# design.net
KiCad netlist of a schematic drawn in Altium Designer
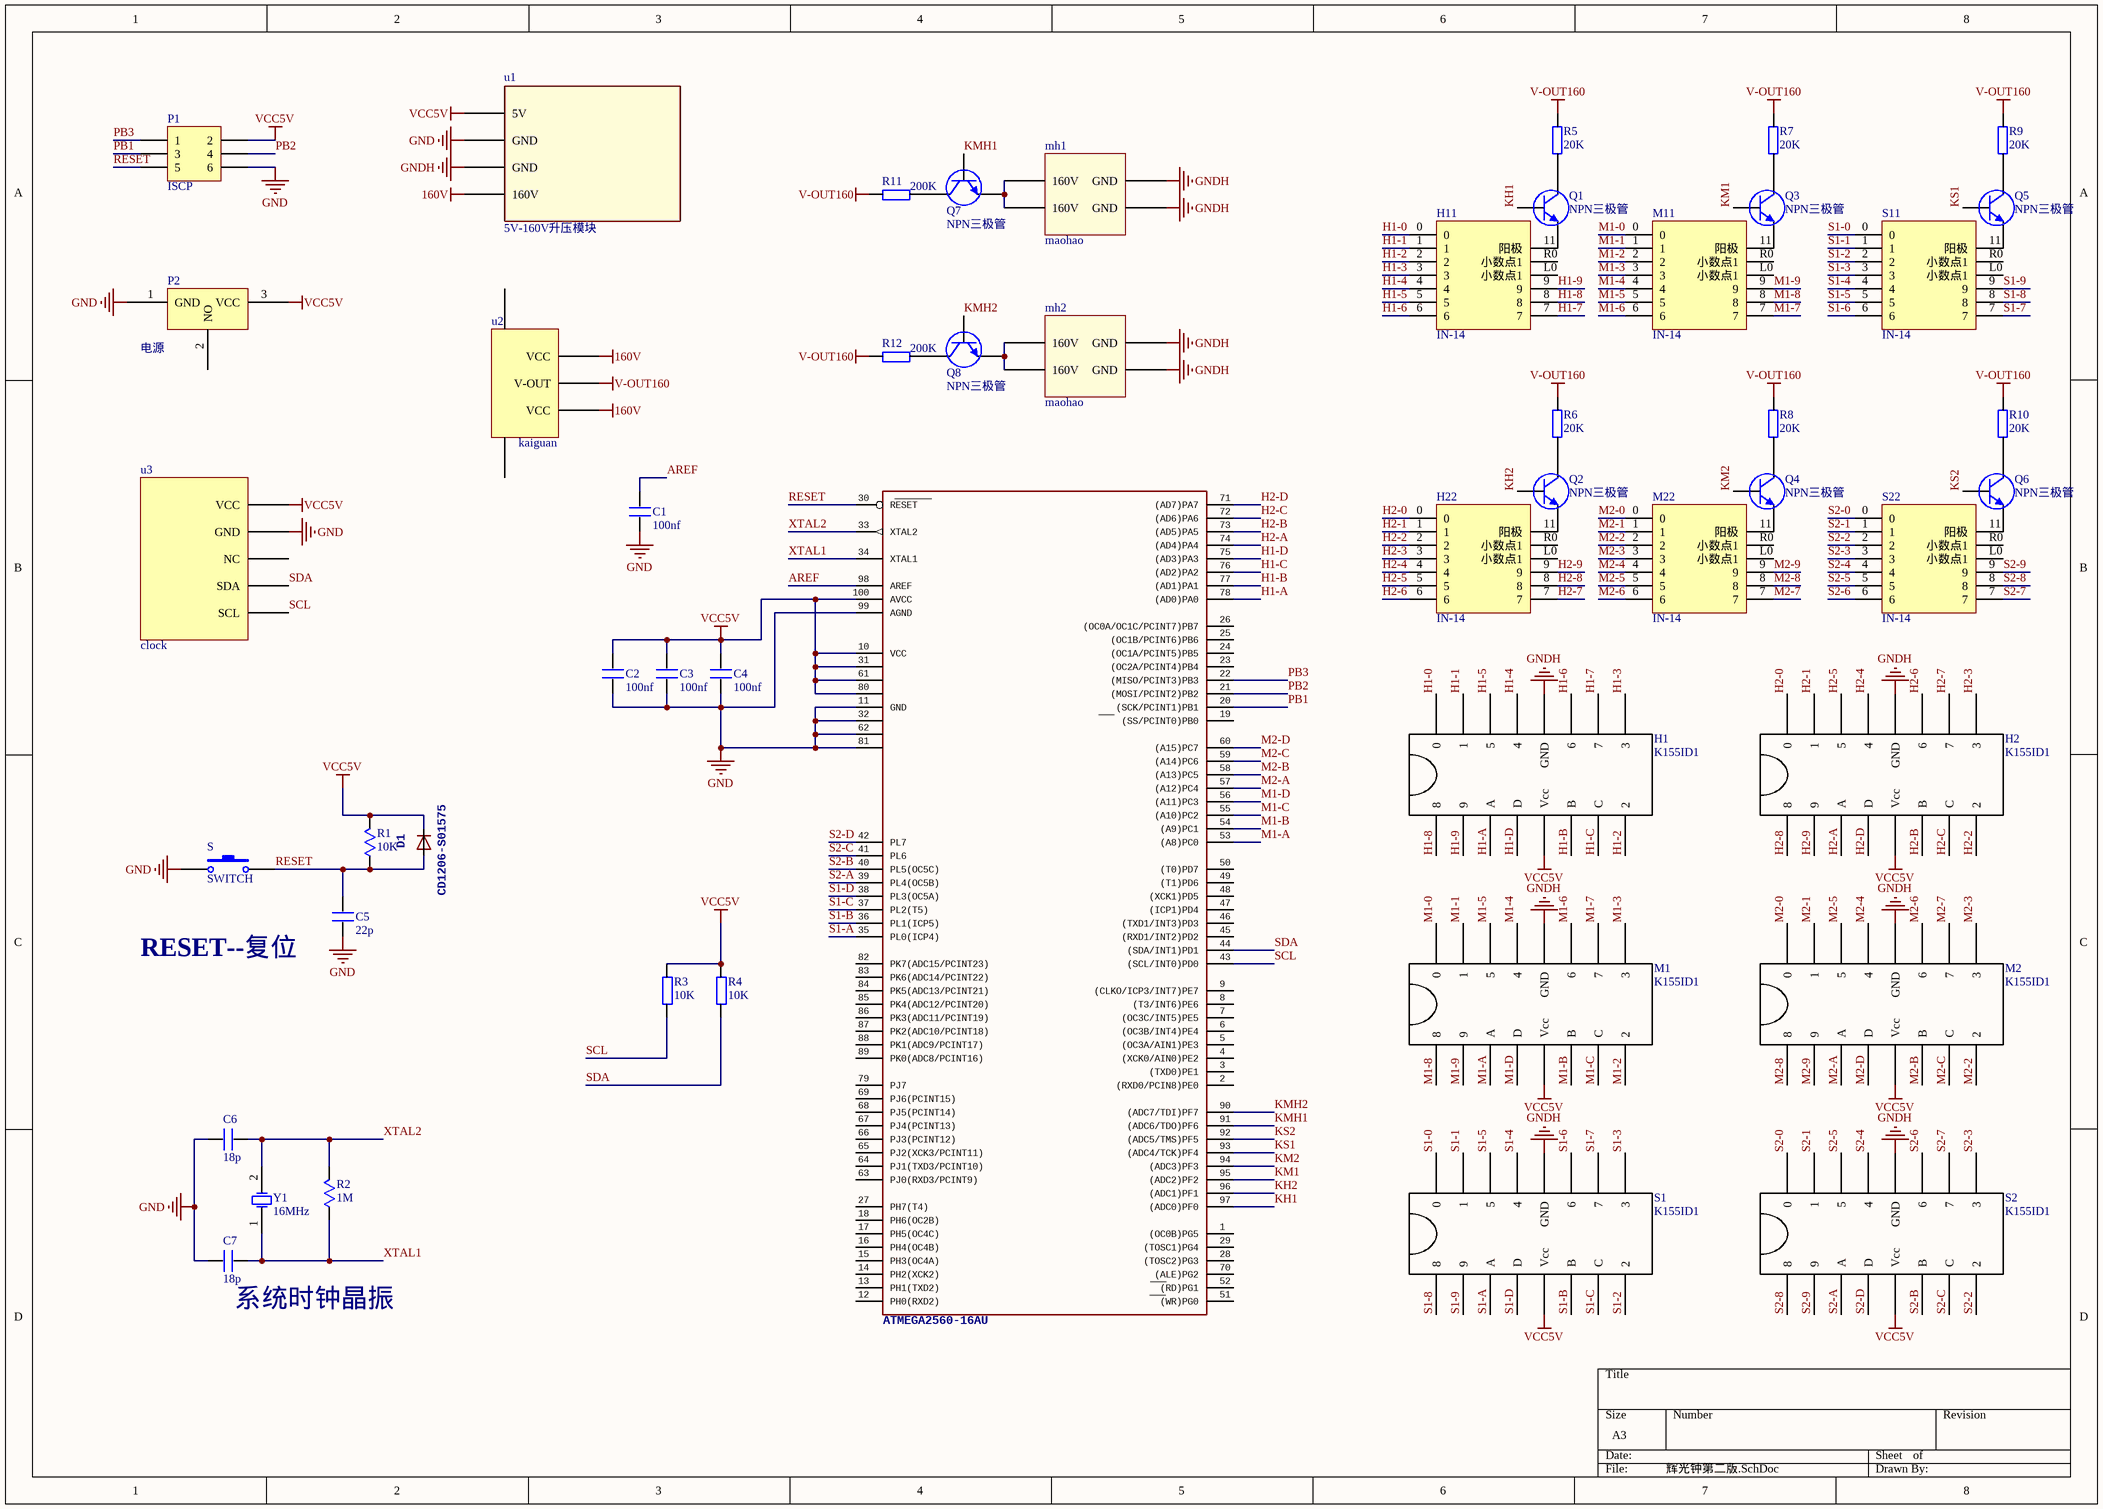
[diagram p0: 辉光钟第二版.SchDoc]

(export (version "E")
  (design (tool "Eeschema 10.0.6"))
  (components
    (comp (ref "C1") (value "100nf") (footprint "0805") (libsource (lib "STM32封装库") (part "C")))
    (comp (ref "C2") (value "100nf") (footprint "0805") (libsource (lib "STM32封装库") (part "C")))
    (comp (ref "C3") (value "100nf") (footprint "0805") (libsource (lib "STM32封装库") (part "C")))
    (comp (ref "C4") (value "100nf") (footprint "0805") (libsource (lib "STM32封装库") (part "C")))
    (comp (ref "C5") (value "22p") (footprint "0805") (libsource (lib "STM32封装库") (part "C_3")))
    (comp (ref "C6") (value "18p") (footprint "0805") (libsource (lib "STM32封装库") (part "C_1")))
    (comp (ref "C7") (value "18p") (footprint "0805") (libsource (lib "STM32封装库") (part "C_1")))
    (comp (ref "D1")
      (value "CD1206-S01575")
      (footprint "MINIMELF")
      (description "<b>DIODE</b>")
      (libsource (lib "Arduino_MEGA_2560-Rev3") (part "DIODE-MINIMELF"))
    )
    (comp (ref "H1")
      (value "K155ID1")
      (footprint "Miscellaneous Devices:DIP-16")
      (libsource (lib "辉光钟第二版") (part "K155ID1"))
    )
    (comp (ref "H2")
      (value "K155ID1")
      (footprint "Miscellaneous Devices:DIP-16")
      (libsource (lib "辉光钟第二版") (part "K155ID1"))
    )
    (comp (ref "H11") (value "IN-14") (footprint "IN-14") (libsource (lib "辉光管时钟V2.0") (part "IN-14")))
    (comp (ref "H22") (value "IN-14") (footprint "IN-14") (libsource (lib "辉光管时钟V2.0") (part "IN-14")))
    (comp (ref "M1")
      (value "K155ID1")
      (footprint "Miscellaneous Devices:DIP-16")
      (libsource (lib "辉光钟第二版") (part "K155ID1"))
    )
    (comp (ref "M2")
      (value "K155ID1")
      (footprint "Miscellaneous Devices:DIP-16")
      (libsource (lib "辉光钟第二版") (part "K155ID1"))
    )
    (comp (ref "M11") (value "IN-14") (footprint "IN-14") (libsource (lib "辉光管时钟V2.0") (part "IN-14")))
    (comp (ref "M22") (value "IN-14") (footprint "IN-14") (libsource (lib "辉光管时钟V2.0") (part "IN-14")))
    (comp (ref "mh1")
      (value "maohao")
      (footprint "maohao:PCBComponent_1")
      (libsource (lib "辉光钟第二版") (part "maohao"))
    )
    (comp (ref "mh2")
      (value "maohao")
      (footprint "maohao:PCBComponent_1")
      (libsource (lib "辉光钟第二版") (part "maohao"))
    )
    (comp (ref "P1")
      (value "ISCP")
      (footprint "HDR2X3")
      (description "Header, 3-Pin, Dual row")
      (fields (field (name "PUBLISHER") "Altium Limited"))
      (libsource (lib "Miscellaneous Connectors") (part "Header 3X2"))
    )
    (comp (ref "P2") (value "电源") (footprint "DC5.5-2.1") (libsource (lib "常用元件库") (part "dc5.5-2.1")))
    (comp (ref "Q1")
      (value "NPN三极管")
      (footprint "TO-92")
      (description "NPN")
      (fields (field (name "PUBLISHER") "Altium Limited"))
      (libsource (lib "三极管集成库") (part "NPN三极管_1"))
    )
    (comp (ref "Q2")
      (value "NPN三极管")
      (footprint "TO-92")
      (description "NPN")
      (fields (field (name "PUBLISHER") "Altium Limited"))
      (libsource (lib "三极管集成库") (part "NPN三极管_1"))
    )
    (comp (ref "Q3")
      (value "NPN三极管")
      (footprint "TO-92")
      (description "NPN")
      (fields (field (name "PUBLISHER") "Altium Limited"))
      (libsource (lib "三极管集成库") (part "NPN三极管_1"))
    )
    (comp (ref "Q4")
      (value "NPN三极管")
      (footprint "TO-92")
      (description "NPN")
      (fields (field (name "PUBLISHER") "Altium Limited"))
      (libsource (lib "三极管集成库") (part "NPN三极管_1"))
    )
    (comp (ref "Q5")
      (value "NPN三极管")
      (footprint "TO-92")
      (description "NPN")
      (fields (field (name "PUBLISHER") "Altium Limited"))
      (libsource (lib "三极管集成库") (part "NPN三极管_1"))
    )
    (comp (ref "Q6")
      (value "NPN三极管")
      (footprint "TO-92")
      (description "NPN")
      (fields (field (name "PUBLISHER") "Altium Limited"))
      (libsource (lib "三极管集成库") (part "NPN三极管_1"))
    )
    (comp (ref "Q7")
      (value "NPN三极管")
      (footprint "TO-92")
      (description "NPN")
      (fields (field (name "PUBLISHER") "Altium Limited"))
      (libsource (lib "三极管集成库") (part "NPN三极管_1"))
    )
    (comp (ref "Q8")
      (value "NPN三极管")
      (footprint "TO-92")
      (description "NPN")
      (fields (field (name "PUBLISHER") "Altium Limited"))
      (libsource (lib "三极管集成库") (part "NPN三极管_1"))
    )
    (comp (ref "R1") (value "10K") (footprint "0805") (libsource (lib "YT1_SCH_99SE") (part "RES")))
    (comp (ref "R2") (value "1M") (footprint "0805") (libsource (lib "YT1_SCH_99SE") (part "RES")))
    (comp (ref "R3") (value "10K") (footprint "0805") (libsource (lib "STM32封装库") (part "R")))
    (comp (ref "R4") (value "10K") (footprint "0805") (libsource (lib "STM32封装库") (part "R")))
    (comp (ref "R5") (value "20K") (footprint "0805") (libsource (lib "STM32封装库") (part "R")))
    (comp (ref "R6") (value "20K") (footprint "0805") (libsource (lib "STM32封装库") (part "R")))
    (comp (ref "R7") (value "20K") (footprint "0805") (libsource (lib "STM32封装库") (part "R")))
    (comp (ref "R8") (value "20K") (footprint "0805") (libsource (lib "STM32封装库") (part "R")))
    (comp (ref "R9") (value "20K") (footprint "0805") (libsource (lib "STM32封装库") (part "R")))
    (comp (ref "R10") (value "20K") (footprint "0805") (libsource (lib "STM32封装库") (part "R")))
    (comp (ref "R11") (value "200K") (footprint "0805") (libsource (lib "STM32封装库") (part "R")))
    (comp (ref "R12") (value "200K") (footprint "0805") (libsource (lib "STM32封装库") (part "R")))
    (comp (ref "S") (value "SWITCH") (footprint "SWITCH") (libsource (lib "STM32封装库") (part "SWITCH")))
    (comp (ref "S1")
      (value "K155ID1")
      (footprint "Miscellaneous Devices:DIP-16")
      (libsource (lib "辉光钟第二版") (part "K155ID1"))
    )
    (comp (ref "S2")
      (value "K155ID1")
      (footprint "Miscellaneous Devices:DIP-16")
      (libsource (lib "辉光钟第二版") (part "K155ID1"))
    )
    (comp (ref "S11") (value "IN-14") (footprint "IN-14") (libsource (lib "辉光管时钟V2.0") (part "IN-14")))
    (comp (ref "S22") (value "IN-14") (footprint "IN-14") (libsource (lib "辉光管时钟V2.0") (part "IN-14")))
    (comp (ref "u0")
      (value "ATMEGA2560-16AU")
      (footprint "TQFP100")
      (libsource (lib "Arduino_MEGA_2560-Rev3") (part "ATMEGA2560AU"))
    )
    (comp (ref "u1")
      (value "5V-160V升压模块")
      (footprint "5-160:PCBComponent_1")
      (libsource (lib "辉光钟第二版") (part "5-160"))
    )
    (comp (ref "u2")
      (value "kaiguan")
      (footprint "kaiguan:PCBComponent_1")
      (libsource (lib "辉光钟第二版") (part "kaiguan"))
    )
    (comp (ref "u3")
      (value "clock")
      (footprint "clock:PCBComponent_1")
      (libsource (lib "辉光钟第二版") (part "clock"))
    )
    (comp (ref "Y1")
      (value "16MHz")
      (footprint "XTAL_US")
      (description "Crystal Oscillator")
      (fields (field (name "PUBLISHER") "Altium Limited"))
      (libsource (lib "STM32封装库") (part "XTAL"))
    )
  )
  (nets
    (net (code "1") (name "/AREF") (class "Default")
      (node (ref "C1") (pin "2") (pintype "passive"))
      (node (ref "u0") (pin "98") (pinfunction "AREF_98") (pintype "passive"))
    )
    (net (code "2") (name "/H1-0") (class "Default")
      (node (ref "H1") (pin "16") (pinfunction "0_16") (pintype "passive"))
      (node (ref "H11") (pin "0") (pinfunction "0_0") (pintype "passive"))
    )
    (net (code "3") (name "/H1-1") (class "Default")
      (node (ref "H1") (pin "15") (pinfunction "1_15") (pintype "passive"))
      (node (ref "H11") (pin "1") (pinfunction "1_1") (pintype "passive"))
    )
    (net (code "4") (name "/H1-2") (class "Default")
      (node (ref "H1") (pin "8") (pinfunction "2_8") (pintype "passive"))
      (node (ref "H11") (pin "2") (pinfunction "2_2") (pintype "passive"))
    )
    (net (code "5") (name "/H1-3") (class "Default")
      (node (ref "H1") (pin "9") (pinfunction "3_9") (pintype "passive"))
      (node (ref "H11") (pin "3") (pinfunction "3_3") (pintype "passive"))
    )
    (net (code "6") (name "/H1-4") (class "Default")
      (node (ref "H1") (pin "13") (pinfunction "4_13") (pintype "passive"))
      (node (ref "H11") (pin "4") (pinfunction "4_4") (pintype "passive"))
    )
    (net (code "7") (name "/H1-5") (class "Default")
      (node (ref "H1") (pin "14") (pinfunction "5_14") (pintype "passive"))
      (node (ref "H11") (pin "5") (pinfunction "5_5") (pintype "passive"))
    )
    (net (code "8") (name "/H1-6") (class "Default")
      (node (ref "H1") (pin "11") (pinfunction "6_11") (pintype "passive"))
      (node (ref "H11") (pin "6") (pinfunction "6_6") (pintype "passive"))
    )
    (net (code "9") (name "/H1-7") (class "Default")
      (node (ref "H1") (pin "10") (pinfunction "7_10") (pintype "passive"))
      (node (ref "H11") (pin "7") (pinfunction "7_7") (pintype "passive"))
    )
    (net (code "10") (name "/H1-8") (class "Default")
      (node (ref "H1") (pin "1") (pinfunction "8_1") (pintype "passive"))
      (node (ref "H11") (pin "8") (pinfunction "8_8") (pintype "passive"))
    )
    (net (code "11") (name "/H1-9") (class "Default")
      (node (ref "H1") (pin "2") (pinfunction "9_2") (pintype "passive"))
      (node (ref "H11") (pin "9") (pinfunction "9_9") (pintype "passive"))
    )
    (net (code "12") (name "/H1-A") (class "Default")
      (node (ref "H1") (pin "3") (pinfunction "A_3") (pintype "passive"))
      (node (ref "u0") (pin "78") (pinfunction "(AD0)PA0_78") (pintype "passive"))
    )
    (net (code "13") (name "/H1-B") (class "Default")
      (node (ref "H1") (pin "6") (pinfunction "B_6") (pintype "passive"))
      (node (ref "u0") (pin "77") (pinfunction "(AD1)PA1_77") (pintype "passive"))
    )
    (net (code "14") (name "/H1-C") (class "Default")
      (node (ref "H1") (pin "7") (pinfunction "C_7") (pintype "passive"))
      (node (ref "u0") (pin "76") (pinfunction "(AD2)PA2_76") (pintype "passive"))
    )
    (net (code "15") (name "/H1-D") (class "Default")
      (node (ref "H1") (pin "4") (pinfunction "D_4") (pintype "passive"))
      (node (ref "u0") (pin "75") (pinfunction "(AD3)PA3_75") (pintype "passive"))
    )
    (net (code "16") (name "/H2-0") (class "Default")
      (node (ref "H2") (pin "16") (pinfunction "0_16") (pintype "passive"))
      (node (ref "H22") (pin "0") (pinfunction "0_0") (pintype "passive"))
    )
    (net (code "17") (name "/H2-1") (class "Default")
      (node (ref "H2") (pin "15") (pinfunction "1_15") (pintype "passive"))
      (node (ref "H22") (pin "1") (pinfunction "1_1") (pintype "passive"))
    )
    (net (code "18") (name "/H2-2") (class "Default")
      (node (ref "H2") (pin "8") (pinfunction "2_8") (pintype "passive"))
      (node (ref "H22") (pin "2") (pinfunction "2_2") (pintype "passive"))
    )
    (net (code "19") (name "/H2-3") (class "Default")
      (node (ref "H2") (pin "9") (pinfunction "3_9") (pintype "passive"))
      (node (ref "H22") (pin "3") (pinfunction "3_3") (pintype "passive"))
    )
    (net (code "20") (name "/H2-4") (class "Default")
      (node (ref "H2") (pin "13") (pinfunction "4_13") (pintype "passive"))
      (node (ref "H22") (pin "4") (pinfunction "4_4") (pintype "passive"))
    )
    (net (code "21") (name "/H2-5") (class "Default")
      (node (ref "H2") (pin "14") (pinfunction "5_14") (pintype "passive"))
      (node (ref "H22") (pin "5") (pinfunction "5_5") (pintype "passive"))
    )
    (net (code "22") (name "/H2-6") (class "Default")
      (node (ref "H2") (pin "11") (pinfunction "6_11") (pintype "passive"))
      (node (ref "H22") (pin "6") (pinfunction "6_6") (pintype "passive"))
    )
    (net (code "23") (name "/H2-7") (class "Default")
      (node (ref "H2") (pin "10") (pinfunction "7_10") (pintype "passive"))
      (node (ref "H22") (pin "7") (pinfunction "7_7") (pintype "passive"))
    )
    (net (code "24") (name "/H2-8") (class "Default")
      (node (ref "H2") (pin "1") (pinfunction "8_1") (pintype "passive"))
      (node (ref "H22") (pin "8") (pinfunction "8_8") (pintype "passive"))
    )
    (net (code "25") (name "/H2-9") (class "Default")
      (node (ref "H2") (pin "2") (pinfunction "9_2") (pintype "passive"))
      (node (ref "H22") (pin "9") (pinfunction "9_9") (pintype "passive"))
    )
    (net (code "26") (name "/H2-A") (class "Default")
      (node (ref "H2") (pin "3") (pinfunction "A_3") (pintype "passive"))
      (node (ref "u0") (pin "74") (pinfunction "(AD4)PA4_74") (pintype "passive"))
    )
    (net (code "27") (name "/H2-B") (class "Default")
      (node (ref "H2") (pin "6") (pinfunction "B_6") (pintype "passive"))
      (node (ref "u0") (pin "73") (pinfunction "(AD5)PA5_73") (pintype "passive"))
    )
    (net (code "28") (name "/H2-C") (class "Default")
      (node (ref "H2") (pin "7") (pinfunction "C_7") (pintype "passive"))
      (node (ref "u0") (pin "72") (pinfunction "(AD6)PA6_72") (pintype "passive"))
    )
    (net (code "29") (name "/H2-D") (class "Default")
      (node (ref "H2") (pin "4") (pinfunction "D_4") (pintype "passive"))
      (node (ref "u0") (pin "71") (pinfunction "(AD7)PA7_71") (pintype "passive"))
    )
    (net (code "30") (name "/KH1") (class "Default")
      (node (ref "Q1") (pin "2") (pinfunction "B_2") (pintype "passive"))
      (node (ref "u0") (pin "97") (pinfunction "(ADC0)PF0_97") (pintype "passive"))
    )
    (net (code "31") (name "/KH2") (class "Default")
      (node (ref "Q2") (pin "2") (pinfunction "B_2") (pintype "passive"))
      (node (ref "u0") (pin "96") (pinfunction "(ADC1)PF1_96") (pintype "passive"))
    )
    (net (code "32") (name "/KM1") (class "Default")
      (node (ref "Q3") (pin "2") (pinfunction "B_2") (pintype "passive"))
      (node (ref "u0") (pin "95") (pinfunction "(ADC2)PF2_95") (pintype "passive"))
    )
    (net (code "33") (name "/KM2") (class "Default")
      (node (ref "Q4") (pin "2") (pinfunction "B_2") (pintype "passive"))
      (node (ref "u0") (pin "94") (pinfunction "(ADC3)PF3_94") (pintype "passive"))
    )
    (net (code "34") (name "/KMH1") (class "Default")
      (node (ref "Q7") (pin "2") (pinfunction "B_2") (pintype "passive"))
      (node (ref "u0") (pin "91") (pinfunction "(ADC6/TDO)PF6_91") (pintype "passive"))
    )
    (net (code "35") (name "/KMH2") (class "Default")
      (node (ref "Q8") (pin "2") (pinfunction "B_2") (pintype "passive"))
      (node (ref "u0") (pin "90") (pinfunction "(ADC7/TDI)PF7_90") (pintype "passive"))
    )
    (net (code "36") (name "/KS1") (class "Default")
      (node (ref "Q5") (pin "2") (pinfunction "B_2") (pintype "passive"))
      (node (ref "u0") (pin "93") (pinfunction "(ADC4/TCK)PF4_93") (pintype "passive"))
    )
    (net (code "37") (name "/KS2") (class "Default")
      (node (ref "Q6") (pin "2") (pinfunction "B_2") (pintype "passive"))
      (node (ref "u0") (pin "92") (pinfunction "(ADC5/TMS)PF5_92") (pintype "passive"))
    )
    (net (code "38") (name "/M1-0") (class "Default")
      (node (ref "M1") (pin "16") (pinfunction "0_16") (pintype "passive"))
      (node (ref "M11") (pin "0") (pinfunction "0_0") (pintype "passive"))
    )
    (net (code "39") (name "/M1-1") (class "Default")
      (node (ref "M1") (pin "15") (pinfunction "1_15") (pintype "passive"))
      (node (ref "M11") (pin "1") (pinfunction "1_1") (pintype "passive"))
    )
    (net (code "40") (name "/M1-2") (class "Default")
      (node (ref "M1") (pin "8") (pinfunction "2_8") (pintype "passive"))
      (node (ref "M11") (pin "2") (pinfunction "2_2") (pintype "passive"))
    )
    (net (code "41") (name "/M1-3") (class "Default")
      (node (ref "M1") (pin "9") (pinfunction "3_9") (pintype "passive"))
      (node (ref "M11") (pin "3") (pinfunction "3_3") (pintype "passive"))
    )
    (net (code "42") (name "/M1-4") (class "Default")
      (node (ref "M1") (pin "13") (pinfunction "4_13") (pintype "passive"))
      (node (ref "M11") (pin "4") (pinfunction "4_4") (pintype "passive"))
    )
    (net (code "43") (name "/M1-5") (class "Default")
      (node (ref "M1") (pin "14") (pinfunction "5_14") (pintype "passive"))
      (node (ref "M11") (pin "5") (pinfunction "5_5") (pintype "passive"))
    )
    (net (code "44") (name "/M1-6") (class "Default")
      (node (ref "M1") (pin "11") (pinfunction "6_11") (pintype "passive"))
      (node (ref "M11") (pin "6") (pinfunction "6_6") (pintype "passive"))
    )
    (net (code "45") (name "/M1-7") (class "Default")
      (node (ref "M1") (pin "10") (pinfunction "7_10") (pintype "passive"))
      (node (ref "M11") (pin "7") (pinfunction "7_7") (pintype "passive"))
    )
    (net (code "46") (name "/M1-8") (class "Default")
      (node (ref "M1") (pin "1") (pinfunction "8_1") (pintype "passive"))
      (node (ref "M11") (pin "8") (pinfunction "8_8") (pintype "passive"))
    )
    (net (code "47") (name "/M1-9") (class "Default")
      (node (ref "M1") (pin "2") (pinfunction "9_2") (pintype "passive"))
      (node (ref "M11") (pin "9") (pinfunction "9_9") (pintype "passive"))
    )
    (net (code "48") (name "/M1-A") (class "Default")
      (node (ref "M1") (pin "3") (pinfunction "A_3") (pintype "passive"))
      (node (ref "u0") (pin "53") (pinfunction "(A8)PC0_53") (pintype "passive"))
    )
    (net (code "49") (name "/M1-B") (class "Default")
      (node (ref "M1") (pin "6") (pinfunction "B_6") (pintype "passive"))
      (node (ref "u0") (pin "54") (pinfunction "(A9)PC1_54") (pintype "passive"))
    )
    (net (code "50") (name "/M1-C") (class "Default")
      (node (ref "M1") (pin "7") (pinfunction "C_7") (pintype "passive"))
      (node (ref "u0") (pin "55") (pinfunction "(A10)PC2_55") (pintype "passive"))
    )
    (net (code "51") (name "/M1-D") (class "Default")
      (node (ref "M1") (pin "4") (pinfunction "D_4") (pintype "passive"))
      (node (ref "u0") (pin "56") (pinfunction "(A11)PC3_56") (pintype "passive"))
    )
    (net (code "52") (name "/M2-0") (class "Default")
      (node (ref "M2") (pin "16") (pinfunction "0_16") (pintype "passive"))
      (node (ref "M22") (pin "0") (pinfunction "0_0") (pintype "passive"))
    )
    (net (code "53") (name "/M2-1") (class "Default")
      (node (ref "M2") (pin "15") (pinfunction "1_15") (pintype "passive"))
      (node (ref "M22") (pin "1") (pinfunction "1_1") (pintype "passive"))
    )
    (net (code "54") (name "/M2-2") (class "Default")
      (node (ref "M2") (pin "8") (pinfunction "2_8") (pintype "passive"))
      (node (ref "M22") (pin "2") (pinfunction "2_2") (pintype "passive"))
    )
    (net (code "55") (name "/M2-3") (class "Default")
      (node (ref "M2") (pin "9") (pinfunction "3_9") (pintype "passive"))
      (node (ref "M22") (pin "3") (pinfunction "3_3") (pintype "passive"))
    )
    (net (code "56") (name "/M2-4") (class "Default")
      (node (ref "M2") (pin "13") (pinfunction "4_13") (pintype "passive"))
      (node (ref "M22") (pin "4") (pinfunction "4_4") (pintype "passive"))
    )
    (net (code "57") (name "/M2-5") (class "Default")
      (node (ref "M2") (pin "14") (pinfunction "5_14") (pintype "passive"))
      (node (ref "M22") (pin "5") (pinfunction "5_5") (pintype "passive"))
    )
    (net (code "58") (name "/M2-6") (class "Default")
      (node (ref "M2") (pin "11") (pinfunction "6_11") (pintype "passive"))
      (node (ref "M22") (pin "6") (pinfunction "6_6") (pintype "passive"))
    )
    (net (code "59") (name "/M2-7") (class "Default")
      (node (ref "M2") (pin "10") (pinfunction "7_10") (pintype "passive"))
      (node (ref "M22") (pin "7") (pinfunction "7_7") (pintype "passive"))
    )
    (net (code "60") (name "/M2-8") (class "Default")
      (node (ref "M2") (pin "1") (pinfunction "8_1") (pintype "passive"))
      (node (ref "M22") (pin "8") (pinfunction "8_8") (pintype "passive"))
    )
    (net (code "61") (name "/M2-9") (class "Default")
      (node (ref "M2") (pin "2") (pinfunction "9_2") (pintype "passive"))
      (node (ref "M22") (pin "9") (pinfunction "9_9") (pintype "passive"))
    )
    (net (code "62") (name "/M2-A") (class "Default")
      (node (ref "M2") (pin "3") (pinfunction "A_3") (pintype "passive"))
      (node (ref "u0") (pin "57") (pinfunction "(A12)PC4_57") (pintype "passive"))
    )
    (net (code "63") (name "/M2-B") (class "Default")
      (node (ref "M2") (pin "6") (pinfunction "B_6") (pintype "passive"))
      (node (ref "u0") (pin "58") (pinfunction "(A13)PC5_58") (pintype "passive"))
    )
    (net (code "64") (name "/M2-C") (class "Default")
      (node (ref "M2") (pin "7") (pinfunction "C_7") (pintype "passive"))
      (node (ref "u0") (pin "59") (pinfunction "(A14)PC6_59") (pintype "passive"))
    )
    (net (code "65") (name "/M2-D") (class "Default")
      (node (ref "M2") (pin "4") (pinfunction "D_4") (pintype "passive"))
      (node (ref "u0") (pin "60") (pinfunction "(A15)PC7_60") (pintype "passive"))
    )
    (net (code "66") (name "/PB1") (class "Default")
      (node (ref "P1") (pin "3") (pinfunction "3_3") (pintype "passive"))
      (node (ref "u0") (pin "20") (pinfunction "(SCK/PCINT1)PB1_20") (pintype "passive"))
    )
    (net (code "67") (name "/PB2") (class "Default")
      (node (ref "P1") (pin "4") (pinfunction "4_4") (pintype "passive"))
      (node (ref "u0") (pin "21") (pinfunction "(MOSI/PCINT2)PB2_21") (pintype "passive"))
    )
    (net (code "68") (name "/PB3") (class "Default")
      (node (ref "P1") (pin "1") (pinfunction "1_1") (pintype "passive"))
      (node (ref "u0") (pin "22") (pinfunction "(MISO/PCINT3)PB3_22") (pintype "passive"))
    )
    (net (code "69") (name "/RESET") (class "Default")
      (node (ref "C5") (pin "2") (pintype "passive"))
      (node (ref "D1") (pin "A") (pinfunction "A_A") (pintype "passive"))
      (node (ref "P1") (pin "5") (pinfunction "5_5") (pintype "passive"))
      (node (ref "R1") (pin "1") (pinfunction "1_1") (pintype "passive"))
      (node (ref "S") (pin "2") (pinfunction "2_2") (pintype "passive"))
      (node (ref "u0") (pin "30") (pinfunction "RESET_30") (pintype "passive"))
    )
    (net (code "70") (name "/S1-0") (class "Default")
      (node (ref "S1") (pin "16") (pinfunction "0_16") (pintype "passive"))
      (node (ref "S11") (pin "0") (pinfunction "0_0") (pintype "passive"))
    )
    (net (code "71") (name "/S1-1") (class "Default")
      (node (ref "S1") (pin "15") (pinfunction "1_15") (pintype "passive"))
      (node (ref "S11") (pin "1") (pinfunction "1_1") (pintype "passive"))
    )
    (net (code "72") (name "/S1-2") (class "Default")
      (node (ref "S1") (pin "8") (pinfunction "2_8") (pintype "passive"))
      (node (ref "S11") (pin "2") (pinfunction "2_2") (pintype "passive"))
    )
    (net (code "73") (name "/S1-3") (class "Default")
      (node (ref "S1") (pin "9") (pinfunction "3_9") (pintype "passive"))
      (node (ref "S11") (pin "3") (pinfunction "3_3") (pintype "passive"))
    )
    (net (code "74") (name "/S1-4") (class "Default")
      (node (ref "S1") (pin "13") (pinfunction "4_13") (pintype "passive"))
      (node (ref "S11") (pin "4") (pinfunction "4_4") (pintype "passive"))
    )
    (net (code "75") (name "/S1-5") (class "Default")
      (node (ref "S1") (pin "14") (pinfunction "5_14") (pintype "passive"))
      (node (ref "S11") (pin "5") (pinfunction "5_5") (pintype "passive"))
    )
    (net (code "76") (name "/S1-6") (class "Default")
      (node (ref "S1") (pin "11") (pinfunction "6_11") (pintype "passive"))
      (node (ref "S11") (pin "6") (pinfunction "6_6") (pintype "passive"))
    )
    (net (code "77") (name "/S1-7") (class "Default")
      (node (ref "S1") (pin "10") (pinfunction "7_10") (pintype "passive"))
      (node (ref "S11") (pin "7") (pinfunction "7_7") (pintype "passive"))
    )
    (net (code "78") (name "/S1-8") (class "Default")
      (node (ref "S1") (pin "1") (pinfunction "8_1") (pintype "passive"))
      (node (ref "S11") (pin "8") (pinfunction "8_8") (pintype "passive"))
    )
    (net (code "79") (name "/S1-9") (class "Default")
      (node (ref "S1") (pin "2") (pinfunction "9_2") (pintype "passive"))
      (node (ref "S11") (pin "9") (pinfunction "9_9") (pintype "passive"))
    )
    (net (code "80") (name "/S1-A") (class "Default")
      (node (ref "S1") (pin "3") (pinfunction "A_3") (pintype "passive"))
      (node (ref "u0") (pin "35") (pinfunction "PL0(ICP4)_35") (pintype "passive"))
    )
    (net (code "81") (name "/S1-B") (class "Default")
      (node (ref "S1") (pin "6") (pinfunction "B_6") (pintype "passive"))
      (node (ref "u0") (pin "36") (pinfunction "PL1(ICP5)_36") (pintype "passive"))
    )
    (net (code "82") (name "/S1-C") (class "Default")
      (node (ref "S1") (pin "7") (pinfunction "C_7") (pintype "passive"))
      (node (ref "u0") (pin "37") (pinfunction "PL2(T5)_37") (pintype "passive"))
    )
    (net (code "83") (name "/S1-D") (class "Default")
      (node (ref "S1") (pin "4") (pinfunction "D_4") (pintype "passive"))
      (node (ref "u0") (pin "38") (pinfunction "PL3(OC5A)_38") (pintype "passive"))
    )
    (net (code "84") (name "/S2-0") (class "Default")
      (node (ref "S2") (pin "16") (pinfunction "0_16") (pintype "passive"))
      (node (ref "S22") (pin "0") (pinfunction "0_0") (pintype "passive"))
    )
    (net (code "85") (name "/S2-1") (class "Default")
      (node (ref "S2") (pin "15") (pinfunction "1_15") (pintype "passive"))
      (node (ref "S22") (pin "1") (pinfunction "1_1") (pintype "passive"))
    )
    (net (code "86") (name "/S2-2") (class "Default")
      (node (ref "S2") (pin "8") (pinfunction "2_8") (pintype "passive"))
      (node (ref "S22") (pin "2") (pinfunction "2_2") (pintype "passive"))
    )
    (net (code "87") (name "/S2-3") (class "Default")
      (node (ref "S2") (pin "9") (pinfunction "3_9") (pintype "passive"))
      (node (ref "S22") (pin "3") (pinfunction "3_3") (pintype "passive"))
    )
    (net (code "88") (name "/S2-4") (class "Default")
      (node (ref "S2") (pin "13") (pinfunction "4_13") (pintype "passive"))
      (node (ref "S22") (pin "4") (pinfunction "4_4") (pintype "passive"))
    )
    (net (code "89") (name "/S2-5") (class "Default")
      (node (ref "S2") (pin "14") (pinfunction "5_14") (pintype "passive"))
      (node (ref "S22") (pin "5") (pinfunction "5_5") (pintype "passive"))
    )
    (net (code "90") (name "/S2-6") (class "Default")
      (node (ref "S2") (pin "11") (pinfunction "6_11") (pintype "passive"))
      (node (ref "S22") (pin "6") (pinfunction "6_6") (pintype "passive"))
    )
    (net (code "91") (name "/S2-7") (class "Default")
      (node (ref "S2") (pin "10") (pinfunction "7_10") (pintype "passive"))
      (node (ref "S22") (pin "7") (pinfunction "7_7") (pintype "passive"))
    )
    (net (code "92") (name "/S2-8") (class "Default")
      (node (ref "S2") (pin "1") (pinfunction "8_1") (pintype "passive"))
      (node (ref "S22") (pin "8") (pinfunction "8_8") (pintype "passive"))
    )
    (net (code "93") (name "/S2-9") (class "Default")
      (node (ref "S2") (pin "2") (pinfunction "9_2") (pintype "passive"))
      (node (ref "S22") (pin "9") (pinfunction "9_9") (pintype "passive"))
    )
    (net (code "94") (name "/S2-A") (class "Default")
      (node (ref "S2") (pin "3") (pinfunction "A_3") (pintype "passive"))
      (node (ref "u0") (pin "39") (pinfunction "PL4(OC5B)_39") (pintype "passive"))
    )
    (net (code "95") (name "/S2-B") (class "Default")
      (node (ref "S2") (pin "6") (pinfunction "B_6") (pintype "passive"))
      (node (ref "u0") (pin "40") (pinfunction "PL5(OC5C)_40") (pintype "passive"))
    )
    (net (code "96") (name "/S2-C") (class "Default")
      (node (ref "S2") (pin "7") (pinfunction "C_7") (pintype "passive"))
      (node (ref "u0") (pin "41") (pinfunction "PL6_41") (pintype "passive"))
    )
    (net (code "97") (name "/S2-D") (class "Default")
      (node (ref "S2") (pin "4") (pinfunction "D_4") (pintype "passive"))
      (node (ref "u0") (pin "42") (pinfunction "PL7_42") (pintype "passive"))
    )
    (net (code "98") (name "/SCL") (class "Default")
      (node (ref "R3") (pin "1") (pintype "passive"))
      (node (ref "u0") (pin "43") (pinfunction "(SCL/INT0)PD0_43") (pintype "passive"))
      (node (ref "u3") (pin "5") (pinfunction "SCL_5") (pintype "passive"))
    )
    (net (code "99") (name "/SDA") (class "Default")
      (node (ref "R4") (pin "1") (pintype "passive"))
      (node (ref "u0") (pin "44") (pinfunction "(SDA/INT1)PD1_44") (pintype "passive"))
      (node (ref "u3") (pin "4") (pinfunction "SDA_4") (pintype "passive"))
    )
    (net (code "100") (name "/XTAL1") (class "Default")
      (node (ref "C7") (pin "2") (pintype "passive"))
      (node (ref "R2") (pin "1") (pinfunction "1_1") (pintype "passive"))
      (node (ref "Y1") (pin "1") (pinfunction "OSC1_1") (pintype "passive"))
      (node (ref "u0") (pin "34") (pinfunction "XTAL1_34") (pintype "passive"))
    )
    (net (code "101") (name "/XTAL2") (class "Default")
      (node (ref "C6") (pin "2") (pintype "passive"))
      (node (ref "R2") (pin "2") (pinfunction "2_2") (pintype "passive"))
      (node (ref "Y1") (pin "2") (pinfunction "OSC2_2") (pintype "passive"))
      (node (ref "u0") (pin "33") (pinfunction "XTAL2_33") (pintype "output"))
    )
    (net (code "102") (name "160V") (class "Default")
      (node (ref "u1") (pin "4") (pinfunction "160V_4") (pintype "passive"))
      (node (ref "u2") (pin "1") (pinfunction "VCC_1") (pintype "passive"))
      (node (ref "u2") (pin "3") (pinfunction "VCC_3") (pintype "passive"))
    )
    (net (code "103") (name "GND") (class "Default")
      (node (ref "C1") (pin "1") (pintype "passive"))
      (node (ref "C2") (pin "1") (pintype "passive"))
      (node (ref "C3") (pin "1") (pintype "passive"))
      (node (ref "C4") (pin "1") (pintype "passive"))
      (node (ref "C5") (pin "1") (pintype "passive"))
      (node (ref "C6") (pin "1") (pintype "passive"))
      (node (ref "C7") (pin "1") (pintype "passive"))
      (node (ref "P1") (pin "6") (pinfunction "6_6") (pintype "passive"))
      (node (ref "P2") (pin "1") (pinfunction "GND_1") (pintype "passive"))
      (node (ref "S") (pin "1") (pinfunction "1_1") (pintype "passive"))
      (node (ref "u0") (pin "11") (pinfunction "GND_11") (pintype "power_in"))
      (node (ref "u0") (pin "32") (pinfunction "GND1_32") (pintype "power_in"))
      (node (ref "u0") (pin "62") (pinfunction "GND2_62") (pintype "power_in"))
      (node (ref "u0") (pin "81") (pinfunction "GND3_81") (pintype "power_in"))
      (node (ref "u0") (pin "99") (pinfunction "AGND_99") (pintype "power_in"))
      (node (ref "u1") (pin "2") (pinfunction "GND_2") (pintype "passive"))
      (node (ref "u3") (pin "2") (pinfunction "GND_2") (pintype "passive"))
    )
    (net (code "104") (name "GNDH") (class "Default")
      (node (ref "H1") (pin "12") (pinfunction "GND_12") (pintype "passive"))
      (node (ref "H2") (pin "12") (pinfunction "GND_12") (pintype "passive"))
      (node (ref "M1") (pin "12") (pinfunction "GND_12") (pintype "passive"))
      (node (ref "M2") (pin "12") (pinfunction "GND_12") (pintype "passive"))
      (node (ref "S1") (pin "12") (pinfunction "GND_12") (pintype "passive"))
      (node (ref "S2") (pin "12") (pinfunction "GND_12") (pintype "passive"))
      (node (ref "mh1") (pin "2") (pinfunction "GND_2") (pintype "passive"))
      (node (ref "mh1") (pin "4") (pinfunction "GND_4") (pintype "passive"))
      (node (ref "mh2") (pin "2") (pinfunction "GND_2") (pintype "passive"))
      (node (ref "mh2") (pin "4") (pinfunction "GND_4") (pintype "passive"))
      (node (ref "u1") (pin "3") (pinfunction "GND_3") (pintype "passive"))
    )
    (net (code "105") (name "Net-(H11-阳极)") (class "Default")
      (node (ref "H11") (pin "11") (pinfunction "阳极_11") (pintype "passive"))
      (node (ref "Q1") (pin "3") (pinfunction "E_3") (pintype "passive"))
    )
    (net (code "106") (name "Net-(H22-阳极)") (class "Default")
      (node (ref "H22") (pin "11") (pinfunction "阳极_11") (pintype "passive"))
      (node (ref "Q2") (pin "3") (pinfunction "E_3") (pintype "passive"))
    )
    (net (code "107") (name "Net-(M11-阳极)") (class "Default")
      (node (ref "M11") (pin "11") (pinfunction "阳极_11") (pintype "passive"))
      (node (ref "Q3") (pin "3") (pinfunction "E_3") (pintype "passive"))
    )
    (net (code "108") (name "Net-(M22-阳极)") (class "Default")
      (node (ref "M22") (pin "11") (pinfunction "阳极_11") (pintype "passive"))
      (node (ref "Q4") (pin "3") (pinfunction "E_3") (pintype "passive"))
    )
    (net (code "109") (name "Net-(Q1-C)") (class "Default")
      (node (ref "Q1") (pin "1") (pinfunction "C_1") (pintype "passive"))
      (node (ref "R5") (pin "2") (pintype "passive"))
    )
    (net (code "110") (name "Net-(Q2-C)") (class "Default")
      (node (ref "Q2") (pin "1") (pinfunction "C_1") (pintype "passive"))
      (node (ref "R6") (pin "2") (pintype "passive"))
    )
    (net (code "111") (name "Net-(Q3-C)") (class "Default")
      (node (ref "Q3") (pin "1") (pinfunction "C_1") (pintype "passive"))
      (node (ref "R7") (pin "2") (pintype "passive"))
    )
    (net (code "112") (name "Net-(Q4-C)") (class "Default")
      (node (ref "Q4") (pin "1") (pinfunction "C_1") (pintype "passive"))
      (node (ref "R8") (pin "2") (pintype "passive"))
    )
    (net (code "113") (name "Net-(Q5-C)") (class "Default")
      (node (ref "Q5") (pin "1") (pinfunction "C_1") (pintype "passive"))
      (node (ref "R9") (pin "2") (pintype "passive"))
    )
    (net (code "114") (name "Net-(Q5-E)") (class "Default")
      (node (ref "Q5") (pin "3") (pinfunction "E_3") (pintype "passive"))
      (node (ref "S11") (pin "11") (pinfunction "阳极_11") (pintype "passive"))
    )
    (net (code "115") (name "Net-(Q6-C)") (class "Default")
      (node (ref "Q6") (pin "1") (pinfunction "C_1") (pintype "passive"))
      (node (ref "R10") (pin "2") (pintype "passive"))
    )
    (net (code "116") (name "Net-(Q6-E)") (class "Default")
      (node (ref "Q6") (pin "3") (pinfunction "E_3") (pintype "passive"))
      (node (ref "S22") (pin "11") (pinfunction "阳极_11") (pintype "passive"))
    )
    (net (code "117") (name "Net-(Q7-C)") (class "Default")
      (node (ref "Q7") (pin "1") (pinfunction "C_1") (pintype "passive"))
      (node (ref "R11") (pin "2") (pintype "passive"))
    )
    (net (code "118") (name "Net-(Q7-E)") (class "Default")
      (node (ref "Q7") (pin "3") (pinfunction "E_3") (pintype "passive"))
      (node (ref "mh1") (pin "1") (pinfunction "160V_1") (pintype "passive"))
      (node (ref "mh1") (pin "3") (pinfunction "160V_3") (pintype "passive"))
    )
    (net (code "119") (name "Net-(Q8-C)") (class "Default")
      (node (ref "Q8") (pin "1") (pinfunction "C_1") (pintype "passive"))
      (node (ref "R12") (pin "2") (pintype "passive"))
    )
    (net (code "120") (name "Net-(Q8-E)") (class "Default")
      (node (ref "Q8") (pin "3") (pinfunction "E_3") (pintype "passive"))
      (node (ref "mh2") (pin "1") (pinfunction "160V_1") (pintype "passive"))
      (node (ref "mh2") (pin "3") (pinfunction "160V_3") (pintype "passive"))
    )
    (net (code "121") (name "V-OUT160") (class "Default")
      (node (ref "R10") (pin "1") (pintype "passive"))
      (node (ref "R11") (pin "1") (pintype "passive"))
      (node (ref "R12") (pin "1") (pintype "passive"))
      (node (ref "R5") (pin "1") (pintype "passive"))
      (node (ref "R6") (pin "1") (pintype "passive"))
      (node (ref "R7") (pin "1") (pintype "passive"))
      (node (ref "R8") (pin "1") (pintype "passive"))
      (node (ref "R9") (pin "1") (pintype "passive"))
      (node (ref "u2") (pin "2") (pinfunction "V-OUT_2") (pintype "passive"))
    )
    (net (code "122") (name "VCC5V") (class "Default")
      (node (ref "C2") (pin "2") (pintype "passive"))
      (node (ref "C3") (pin "2") (pintype "passive"))
      (node (ref "C4") (pin "2") (pintype "passive"))
      (node (ref "D1") (pin "C") (pinfunction "C_C") (pintype "passive"))
      (node (ref "H1") (pin "5") (pinfunction "Vcc_5") (pintype "passive"))
      (node (ref "H2") (pin "5") (pinfunction "Vcc_5") (pintype "passive"))
      (node (ref "M1") (pin "5") (pinfunction "Vcc_5") (pintype "passive"))
      (node (ref "M2") (pin "5") (pinfunction "Vcc_5") (pintype "passive"))
      (node (ref "P1") (pin "2") (pinfunction "2_2") (pintype "passive"))
      (node (ref "P2") (pin "3") (pinfunction "VCC_3") (pintype "passive"))
      (node (ref "R1") (pin "2") (pinfunction "2_2") (pintype "passive"))
      (node (ref "R3") (pin "2") (pintype "passive"))
      (node (ref "R4") (pin "2") (pintype "passive"))
      (node (ref "S1") (pin "5") (pinfunction "Vcc_5") (pintype "passive"))
      (node (ref "S2") (pin "5") (pinfunction "Vcc_5") (pintype "passive"))
      (node (ref "u0") (pin "10") (pinfunction "VCC_10") (pintype "power_in"))
      (node (ref "u0") (pin "100") (pinfunction "AVCC_100") (pintype "power_in"))
      (node (ref "u0") (pin "31") (pinfunction "VCC1_31") (pintype "power_in"))
      (node (ref "u0") (pin "61") (pinfunction "VCC2_61") (pintype "power_in"))
      (node (ref "u0") (pin "80") (pinfunction "VCC3_80") (pintype "power_in"))
      (node (ref "u1") (pin "1") (pinfunction "5V_1") (pintype "passive"))
      (node (ref "u3") (pin "1") (pinfunction "VCC_1") (pintype "passive"))
    )
    (net (code "123") (name "unconnected-(H11-小数点1-PadL0)") (class "Default")
      (node (ref "H11") (pin "L0") (pinfunction "小数点1_L0") (pintype "passive"))
    )
    (net (code "124") (name "unconnected-(H11-小数点1-PadR0)") (class "Default")
      (node (ref "H11") (pin "R0") (pinfunction "小数点1_R0") (pintype "passive"))
    )
    (net (code "125") (name "unconnected-(H22-小数点1-PadL0)") (class "Default")
      (node (ref "H22") (pin "L0") (pinfunction "小数点1_L0") (pintype "passive"))
    )
    (net (code "126") (name "unconnected-(H22-小数点1-PadR0)") (class "Default")
      (node (ref "H22") (pin "R0") (pinfunction "小数点1_R0") (pintype "passive"))
    )
    (net (code "127") (name "unconnected-(M11-小数点1-PadL0)") (class "Default")
      (node (ref "M11") (pin "L0") (pinfunction "小数点1_L0") (pintype "passive"))
    )
    (net (code "128") (name "unconnected-(M11-小数点1-PadR0)") (class "Default")
      (node (ref "M11") (pin "R0") (pinfunction "小数点1_R0") (pintype "passive"))
    )
    (net (code "129") (name "unconnected-(M22-小数点1-PadL0)") (class "Default")
      (node (ref "M22") (pin "L0") (pinfunction "小数点1_L0") (pintype "passive"))
    )
    (net (code "130") (name "unconnected-(M22-小数点1-PadR0)") (class "Default")
      (node (ref "M22") (pin "R0") (pinfunction "小数点1_R0") (pintype "passive"))
    )
    (net (code "131") (name "unconnected-(P2-NO-Pad2)") (class "Default")
      (node (ref "P2") (pin "2") (pinfunction "NO_2") (pintype "passive"))
    )
    (net (code "132") (name "unconnected-(S11-小数点1-PadL0)") (class "Default")
      (node (ref "S11") (pin "L0") (pinfunction "小数点1_L0") (pintype "passive"))
    )
    (net (code "133") (name "unconnected-(S11-小数点1-PadR0)") (class "Default")
      (node (ref "S11") (pin "R0") (pinfunction "小数点1_R0") (pintype "passive"))
    )
    (net (code "134") (name "unconnected-(S22-小数点1-PadL0)") (class "Default")
      (node (ref "S22") (pin "L0") (pinfunction "小数点1_L0") (pintype "passive"))
    )
    (net (code "135") (name "unconnected-(S22-小数点1-PadR0)") (class "Default")
      (node (ref "S22") (pin "R0") (pinfunction "小数点1_R0") (pintype "passive"))
    )
    (net (code "136") (name "unconnected-(u0-(ALE)PG2-Pad70)") (class "Default")
      (node (ref "u0") (pin "70") (pinfunction "(ALE)PG2_70") (pintype "passive"))
    )
    (net (code "137") (name "unconnected-(u0-(CLKO{slash}ICP3{slash}INT7)PE7-Pad9)") (class "Default")
      (node (ref "u0") (pin "9") (pinfunction "(CLKO/ICP3/INT7)PE7_9") (pintype "passive"))
    )
    (net (code "138") (name "unconnected-(u0-(ICP1)PD4-Pad47)") (class "Default")
      (node (ref "u0") (pin "47") (pinfunction "(ICP1)PD4_47") (pintype "passive"))
    )
    (net (code "139") (name "unconnected-(u0-(OC0A{slash}OC1C{slash}PCINT7)PB7-Pad26)") (class "Default")
      (node (ref "u0") (pin "26") (pinfunction "(OC0A/OC1C/PCINT7)PB7_26") (pintype "passive"))
    )
    (net (code "140") (name "unconnected-(u0-(OC0B)PG5-Pad1)") (class "Default")
      (node (ref "u0") (pin "1") (pinfunction "(OC0B)PG5_1") (pintype "passive"))
    )
    (net (code "141") (name "unconnected-(u0-(OC1A{slash}PCINT5)PB5-Pad24)") (class "Default")
      (node (ref "u0") (pin "24") (pinfunction "(OC1A/PCINT5)PB5_24") (pintype "passive"))
    )
    (net (code "142") (name "unconnected-(u0-(OC1B{slash}PCINT6)PB6-Pad25)") (class "Default")
      (node (ref "u0") (pin "25") (pinfunction "(OC1B/PCINT6)PB6_25") (pintype "passive"))
    )
    (net (code "143") (name "unconnected-(u0-(OC2A{slash}PCINT4)PB4-Pad23)") (class "Default")
      (node (ref "u0") (pin "23") (pinfunction "(OC2A/PCINT4)PB4_23") (pintype "passive"))
    )
    (net (code "144") (name "unconnected-(u0-(OC3A{slash}AIN1)PE3-Pad5)") (class "Default")
      (node (ref "u0") (pin "5") (pinfunction "(OC3A/AIN1)PE3_5") (pintype "passive"))
    )
    (net (code "145") (name "unconnected-(u0-(OC3B{slash}INT4)PE4-Pad6)") (class "Default")
      (node (ref "u0") (pin "6") (pinfunction "(OC3B/INT4)PE4_6") (pintype "passive"))
    )
    (net (code "146") (name "unconnected-(u0-(OC3C{slash}INT5)PE5-Pad7)") (class "Default")
      (node (ref "u0") (pin "7") (pinfunction "(OC3C/INT5)PE5_7") (pintype "passive"))
    )
    (net (code "147") (name "unconnected-(u0-(RD)PG1-Pad52)") (class "Default")
      (node (ref "u0") (pin "52") (pinfunction "(RD)PG1_52") (pintype "passive"))
    )
    (net (code "148") (name "unconnected-(u0-(RXD0{slash}PCIN8)PE0-Pad2)") (class "Default")
      (node (ref "u0") (pin "2") (pinfunction "(RXD0/PCIN8)PE0_2") (pintype "passive"))
    )
    (net (code "149") (name "unconnected-(u0-(RXD1{slash}INT2)PD2-Pad45)") (class "Default")
      (node (ref "u0") (pin "45") (pinfunction "(RXD1/INT2)PD2_45") (pintype "passive"))
    )
    (net (code "150") (name "unconnected-(u0-(SS{slash}PCINT0)PB0-Pad19)") (class "Default")
      (node (ref "u0") (pin "19") (pinfunction "(SS/PCINT0)PB0_19") (pintype "passive"))
    )
    (net (code "151") (name "unconnected-(u0-(T0)PD7-Pad50)") (class "Default")
      (node (ref "u0") (pin "50") (pinfunction "(T0)PD7_50") (pintype "passive"))
    )
    (net (code "152") (name "unconnected-(u0-(T1)PD6-Pad49)") (class "Default")
      (node (ref "u0") (pin "49") (pinfunction "(T1)PD6_49") (pintype "passive"))
    )
    (net (code "153") (name "unconnected-(u0-(T3{slash}INT6)PE6-Pad8)") (class "Default")
      (node (ref "u0") (pin "8") (pinfunction "(T3/INT6)PE6_8") (pintype "passive"))
    )
    (net (code "154") (name "unconnected-(u0-(TOSC1)PG4-Pad29)") (class "Default")
      (node (ref "u0") (pin "29") (pinfunction "(TOSC1)PG4_29") (pintype "passive"))
    )
    (net (code "155") (name "unconnected-(u0-(TOSC2)PG3-Pad28)") (class "Default")
      (node (ref "u0") (pin "28") (pinfunction "(TOSC2)PG3_28") (pintype "passive"))
    )
    (net (code "156") (name "unconnected-(u0-(TXD0)PE1-Pad3)") (class "Default")
      (node (ref "u0") (pin "3") (pinfunction "(TXD0)PE1_3") (pintype "passive"))
    )
    (net (code "157") (name "unconnected-(u0-(TXD1{slash}INT3)PD3-Pad46)") (class "Default")
      (node (ref "u0") (pin "46") (pinfunction "(TXD1/INT3)PD3_46") (pintype "passive"))
    )
    (net (code "158") (name "unconnected-(u0-(WR)PG0-Pad51)") (class "Default")
      (node (ref "u0") (pin "51") (pinfunction "(WR)PG0_51") (pintype "passive"))
    )
    (net (code "159") (name "unconnected-(u0-(XCK0{slash}AIN0)PE2-Pad4)") (class "Default")
      (node (ref "u0") (pin "4") (pinfunction "(XCK0/AIN0)PE2_4") (pintype "passive"))
    )
    (net (code "160") (name "unconnected-(u0-(XCK1)PD5-Pad48)") (class "Default")
      (node (ref "u0") (pin "48") (pinfunction "(XCK1)PD5_48") (pintype "passive"))
    )
    (net (code "161") (name "unconnected-(u0-PH0(RXD2)-Pad12)") (class "Default")
      (node (ref "u0") (pin "12") (pinfunction "PH0(RXD2)_12") (pintype "passive"))
    )
    (net (code "162") (name "unconnected-(u0-PH1(TXD2)-Pad13)") (class "Default")
      (node (ref "u0") (pin "13") (pinfunction "PH1(TXD2)_13") (pintype "passive"))
    )
    (net (code "163") (name "unconnected-(u0-PH2(XCK2)-Pad14)") (class "Default")
      (node (ref "u0") (pin "14") (pinfunction "PH2(XCK2)_14") (pintype "passive"))
    )
    (net (code "164") (name "unconnected-(u0-PH3(OC4A)-Pad15)") (class "Default")
      (node (ref "u0") (pin "15") (pinfunction "PH3(OC4A)_15") (pintype "passive"))
    )
    (net (code "165") (name "unconnected-(u0-PH4(OC4B)-Pad16)") (class "Default")
      (node (ref "u0") (pin "16") (pinfunction "PH4(OC4B)_16") (pintype "passive"))
    )
    (net (code "166") (name "unconnected-(u0-PH5(OC4C)-Pad17)") (class "Default")
      (node (ref "u0") (pin "17") (pinfunction "PH5(OC4C)_17") (pintype "passive"))
    )
    (net (code "167") (name "unconnected-(u0-PH6(OC2B)-Pad18)") (class "Default")
      (node (ref "u0") (pin "18") (pinfunction "PH6(OC2B)_18") (pintype "passive"))
    )
    (net (code "168") (name "unconnected-(u0-PH7(T4)-Pad27)") (class "Default")
      (node (ref "u0") (pin "27") (pinfunction "PH7(T4)_27") (pintype "passive"))
    )
    (net (code "169") (name "unconnected-(u0-PJ0(RXD3{slash}PCINT9)-Pad63)") (class "Default")
      (node (ref "u0") (pin "63") (pinfunction "PJ0(RXD3/PCINT9)_63") (pintype "passive"))
    )
    (net (code "170") (name "unconnected-(u0-PJ1(TXD3{slash}PCINT10)-Pad64)") (class "Default")
      (node (ref "u0") (pin "64") (pinfunction "PJ1(TXD3/PCINT10)_64") (pintype "passive"))
    )
    (net (code "171") (name "unconnected-(u0-PJ2(XCK3{slash}PCINT11)-Pad65)") (class "Default")
      (node (ref "u0") (pin "65") (pinfunction "PJ2(XCK3/PCINT11)_65") (pintype "passive"))
    )
    (net (code "172") (name "unconnected-(u0-PJ3(PCINT12)-Pad66)") (class "Default")
      (node (ref "u0") (pin "66") (pinfunction "PJ3(PCINT12)_66") (pintype "passive"))
    )
    (net (code "173") (name "unconnected-(u0-PJ4(PCINT13)-Pad67)") (class "Default")
      (node (ref "u0") (pin "67") (pinfunction "PJ4(PCINT13)_67") (pintype "passive"))
    )
    (net (code "174") (name "unconnected-(u0-PJ5(PCINT14)-Pad68)") (class "Default")
      (node (ref "u0") (pin "68") (pinfunction "PJ5(PCINT14)_68") (pintype "passive"))
    )
    (net (code "175") (name "unconnected-(u0-PJ6(PCINT15)-Pad69)") (class "Default")
      (node (ref "u0") (pin "69") (pinfunction "PJ6(PCINT15)_69") (pintype "passive"))
    )
    (net (code "176") (name "unconnected-(u0-PJ7-Pad79)") (class "Default")
      (node (ref "u0") (pin "79") (pinfunction "PJ7_79") (pintype "passive"))
    )
    (net (code "177") (name "unconnected-(u0-PK0(ADC8{slash}PCINT16)-Pad89)") (class "Default")
      (node (ref "u0") (pin "89") (pinfunction "PK0(ADC8/PCINT16)_89") (pintype "passive"))
    )
    (net (code "178") (name "unconnected-(u0-PK1(ADC9{slash}PCINT17)-Pad88)") (class "Default")
      (node (ref "u0") (pin "88") (pinfunction "PK1(ADC9/PCINT17)_88") (pintype "passive"))
    )
    (net (code "179") (name "unconnected-(u0-PK2(ADC10{slash}PCINT18)-Pad87)") (class "Default")
      (node (ref "u0") (pin "87") (pinfunction "PK2(ADC10/PCINT18)_87") (pintype "passive"))
    )
    (net (code "180") (name "unconnected-(u0-PK3(ADC11{slash}PCINT19)-Pad86)") (class "Default")
      (node (ref "u0") (pin "86") (pinfunction "PK3(ADC11/PCINT19)_86") (pintype "passive"))
    )
    (net (code "181") (name "unconnected-(u0-PK4(ADC12{slash}PCINT20)-Pad85)") (class "Default")
      (node (ref "u0") (pin "85") (pinfunction "PK4(ADC12/PCINT20)_85") (pintype "passive"))
    )
    (net (code "182") (name "unconnected-(u0-PK5(ADC13{slash}PCINT21)-Pad84)") (class "Default")
      (node (ref "u0") (pin "84") (pinfunction "PK5(ADC13/PCINT21)_84") (pintype "passive"))
    )
    (net (code "183") (name "unconnected-(u0-PK6(ADC14{slash}PCINT22)-Pad83)") (class "Default")
      (node (ref "u0") (pin "83") (pinfunction "PK6(ADC14/PCINT22)_83") (pintype "passive"))
    )
    (net (code "184") (name "unconnected-(u0-PK7(ADC15{slash}PCINT23)-Pad82)") (class "Default")
      (node (ref "u0") (pin "82") (pinfunction "PK7(ADC15/PCINT23)_82") (pintype "passive"))
    )
    (net (code "185") (name "unconnected-(u2-Pad4)") (class "Default")
      (node (ref "u2") (pin "4") (pinfunction "4_4") (pintype "passive"))
    )
    (net (code "186") (name "unconnected-(u2-Pad5)") (class "Default")
      (node (ref "u2") (pin "5") (pinfunction "5_5") (pintype "passive"))
    )
    (net (code "187") (name "unconnected-(u3-NC-Pad3)") (class "Default")
      (node (ref "u3") (pin "3") (pinfunction "NC_3") (pintype "passive"))
    )
  )
)
